# AlarmScrape.net
KiCad netlist of a schematic drawn in EAGLE
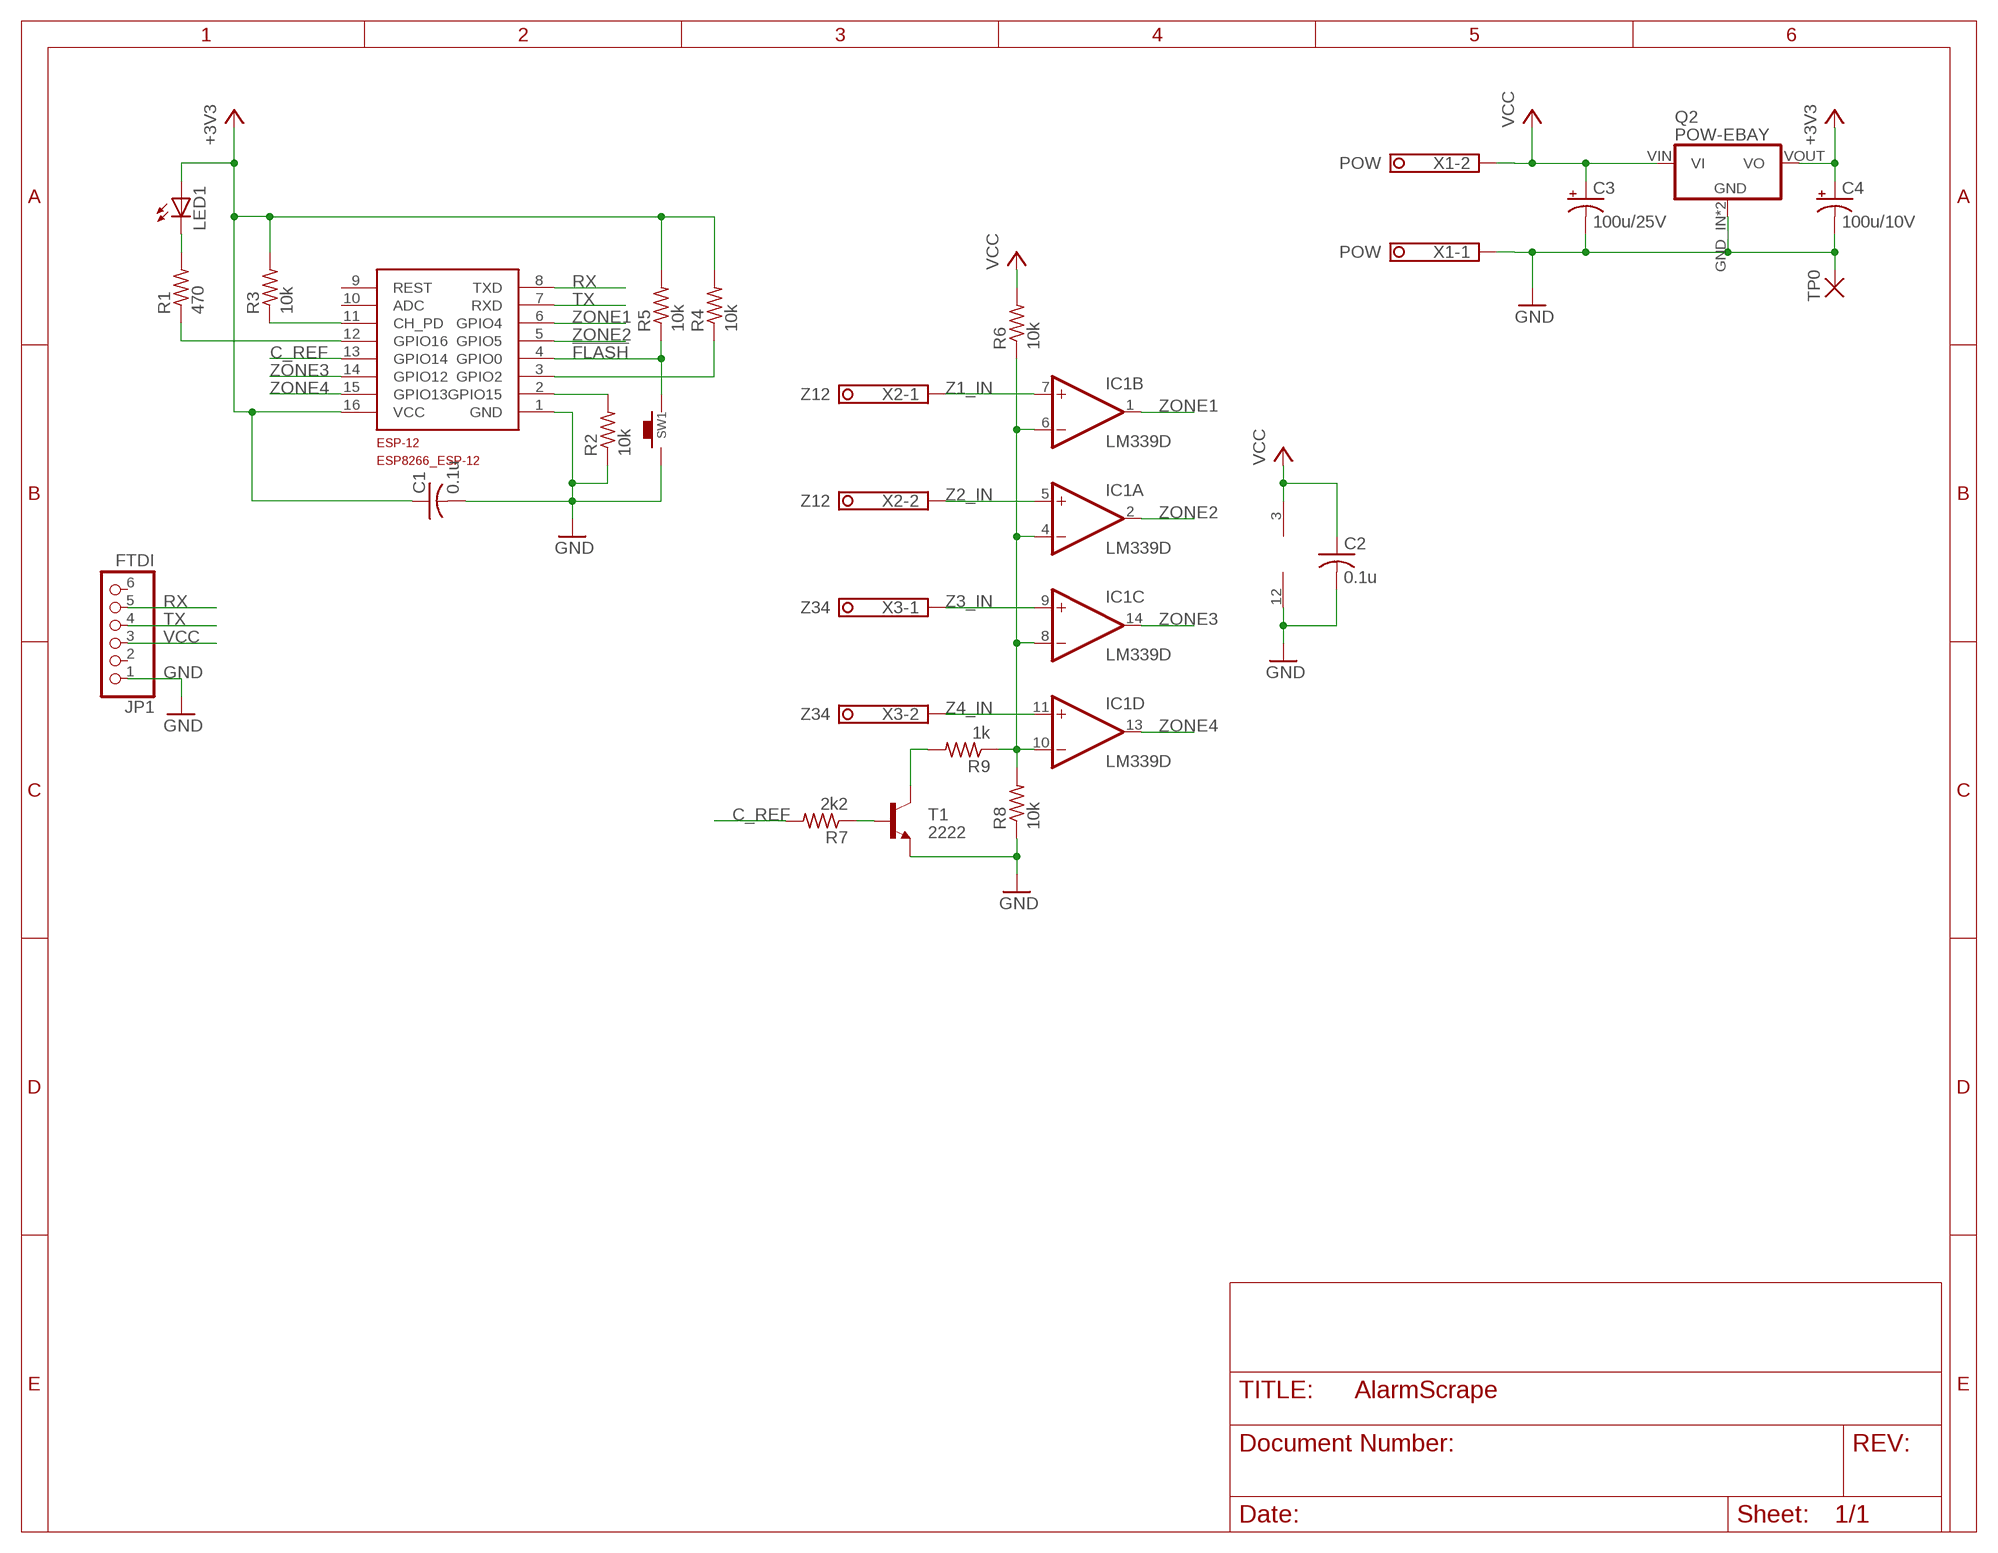
[diagram p0: schematic, sheet 1]

(export (version "E")
  (design (tool "Eeschema 10.0.6"))
  (components
    (comp (ref "C1")
      (value "0.1u")
      (footprint "eagle-import:C0805")
      (libsource (lib "eagle-import") (part "C-USC0805"))
    )
    (comp (ref "C2")
      (value "0.1u")
      (footprint "eagle-import:C0805")
      (libsource (lib "eagle-import") (part "C-USC0805"))
    )
    (comp (ref "C3")
      (value "100u/25V")
      (footprint "eagle-import:E2,5-6")
      (libsource (lib "eagle-import") (part "CPOL-USE2.5-6"))
    )
    (comp (ref "C4")
      (value "100u/10V")
      (footprint "eagle-import:E2,5-6")
      (libsource (lib "eagle-import") (part "CPOL-USE2.5-6"))
    )
    (comp (ref "ESP-12")
      (value "ESP8266_ESP-12")
      (footprint "eagle-import:ESP8266-ESP12")
      (libsource (lib "eagle-import") (part "ESP8266_ESP-12"))
    )
    (comp (ref "IC1")
      (value "LM339D")
      (footprint "eagle-import:SO14")
      (libsource (lib "eagle-import") (part "LM339D"))
    )
    (comp (ref "JP1")
      (value "FTDI")
      (footprint "eagle-import:1X06")
      (libsource (lib "eagle-import") (part "PINHD-1X6"))
    )
    (comp (ref "LED1")
      (value "LEDCHIPLED_0805")
      (footprint "eagle-import:CHIPLED_0805")
      (libsource (lib "eagle-import") (part "LEDCHIPLED_0805"))
    )
    (comp (ref "Q2")
      (value "POW-EBAY")
      (footprint "eagle-import:POW-BUCK-EBAY")
      (libsource (lib "eagle-import") (part "POW-EBAY"))
    )
    (comp (ref "R1")
      (value "470")
      (footprint "eagle-import:R0805")
      (libsource (lib "eagle-import") (part "R-US_R0805"))
    )
    (comp (ref "R2")
      (value "10k")
      (footprint "eagle-import:R0805")
      (libsource (lib "eagle-import") (part "R-US_R0805"))
    )
    (comp (ref "R3")
      (value "10k")
      (footprint "eagle-import:R0805")
      (libsource (lib "eagle-import") (part "R-US_R0805"))
    )
    (comp (ref "R4")
      (value "10k")
      (footprint "eagle-import:R0805")
      (libsource (lib "eagle-import") (part "R-US_R0805"))
    )
    (comp (ref "R5")
      (value "10k")
      (footprint "eagle-import:R0805")
      (libsource (lib "eagle-import") (part "R-US_R0805"))
    )
    (comp (ref "R6")
      (value "10k")
      (footprint "eagle-import:R0805")
      (libsource (lib "eagle-import") (part "R-US_R0805"))
    )
    (comp (ref "R7")
      (value "2k2")
      (footprint "eagle-import:R0805")
      (libsource (lib "eagle-import") (part "R-US_R0805"))
    )
    (comp (ref "R8")
      (value "10k")
      (footprint "eagle-import:R0805")
      (libsource (lib "eagle-import") (part "R-US_R0805"))
    )
    (comp (ref "R9")
      (value "1k")
      (footprint "eagle-import:R0805")
      (libsource (lib "eagle-import") (part "R-US_R0805"))
    )
    (comp (ref "SW1")
      (value "FLASH")
      (footprint "eagle-import:TACT-4X3")
      (libsource (lib "eagle-import") (part "TACTILE-2"))
    )
    (comp (ref "T1")
      (value "2222")
      (footprint "eagle-import:SOT23-3")
      (libsource (lib "eagle-import") (part "TRANSISTOR_NPNSOT23-3"))
    )
    (comp (ref "TP0")
      (value "THROUGH-HOLE")
      (footprint "eagle-import:PAD-032")
      (libsource (lib "eagle-import") (part "THROUGH-HOLE"))
    )
    (comp (ref "X1")
      (value "POW")
      (footprint "eagle-import:1751248")
      (libsource (lib "eagle-import") (part "1751248"))
    )
    (comp (ref "X2")
      (value "Z12")
      (footprint "eagle-import:1751248")
      (libsource (lib "eagle-import") (part "1751248"))
    )
    (comp (ref "X3")
      (value "Z34")
      (footprint "eagle-import:1751248")
      (libsource (lib "eagle-import") (part "1751248"))
    )
  )
  (nets
    (net (code "1") (name "+3V3") (class "Default")
      (node (ref "C1") (pin "1") (pinfunction "1_1") (pintype "passive"))
      (node (ref "C4") (pin "+") (pinfunction "+_+") (pintype "passive"))
      (node (ref "ESP-12") (pin "16") (pinfunction "VCC_16") (pintype "bidirectional"))
      (node (ref "LED1") (pin "A") (pinfunction "A_A") (pintype "passive"))
      (node (ref "Q2") (pin "VOUT") (pinfunction "VO_VOUT") (pintype "passive"))
      (node (ref "R3") (pin "2") (pinfunction "2_2") (pintype "passive"))
      (node (ref "R4") (pin "2") (pinfunction "2_2") (pintype "passive"))
      (node (ref "R5") (pin "2") (pinfunction "2_2") (pintype "passive"))
    )
    (net (code "2") (name "/C_REF") (class "Default")
      (node (ref "ESP-12") (pin "13") (pinfunction "GPIO14_13") (pintype "bidirectional"))
      (node (ref "R7") (pin "2") (pinfunction "2_2") (pintype "passive"))
    )
    (net (code "3") (name "/RX") (class "Default")
      (node (ref "ESP-12") (pin "8") (pinfunction "TXD_8") (pintype "bidirectional"))
      (node (ref "JP1") (pin "5") (pinfunction "5_5") (pintype "passive"))
    )
    (net (code "4") (name "/TX") (class "Default")
      (node (ref "ESP-12") (pin "7") (pinfunction "RXD_7") (pintype "bidirectional"))
      (node (ref "JP1") (pin "4") (pinfunction "4_4") (pintype "passive"))
    )
    (net (code "5") (name "/Z1_IN") (class "Default")
      (node (ref "IC1") (pin "7") (pinfunction "+IN_7") (pintype "input"))
      (node (ref "X2") (pin "1") (pinfunction "K_1") (pintype "passive"))
    )
    (net (code "6") (name "/Z2_IN") (class "Default")
      (node (ref "IC1") (pin "5") (pinfunction "+IN_5") (pintype "input"))
      (node (ref "X2") (pin "2") (pinfunction "K_2") (pintype "passive"))
    )
    (net (code "7") (name "/Z3_IN") (class "Default")
      (node (ref "IC1") (pin "9") (pinfunction "+IN_9") (pintype "input"))
      (node (ref "X3") (pin "1") (pinfunction "K_1") (pintype "passive"))
    )
    (net (code "8") (name "/Z4_IN") (class "Default")
      (node (ref "IC1") (pin "11") (pinfunction "+IN_11") (pintype "input"))
      (node (ref "X3") (pin "2") (pinfunction "K_2") (pintype "passive"))
    )
    (net (code "9") (name "/ZONE1") (class "Default")
      (node (ref "ESP-12") (pin "6") (pinfunction "GPIO4_6") (pintype "bidirectional"))
      (node (ref "IC1") (pin "1") (pinfunction "OUT_1") (pintype "open_collector"))
    )
    (net (code "10") (name "/ZONE2") (class "Default")
      (node (ref "ESP-12") (pin "5") (pinfunction "GPIO5_5") (pintype "bidirectional"))
      (node (ref "IC1") (pin "2") (pinfunction "OUT_2") (pintype "open_collector"))
    )
    (net (code "11") (name "/ZONE3") (class "Default")
      (node (ref "ESP-12") (pin "14") (pinfunction "GPIO12_14") (pintype "bidirectional"))
      (node (ref "IC1") (pin "14") (pinfunction "OUT_14") (pintype "open_collector"))
    )
    (net (code "12") (name "/ZONE4") (class "Default")
      (node (ref "ESP-12") (pin "15") (pinfunction "GPIO13_15") (pintype "bidirectional"))
      (node (ref "IC1") (pin "13") (pinfunction "OUT_13") (pintype "open_collector"))
    )
    (net (code "13") (name "/~{FLASH}") (class "Default")
      (node (ref "ESP-12") (pin "4") (pinfunction "GPIO0_4") (pintype "bidirectional"))
      (node (ref "R5") (pin "1") (pinfunction "1_1") (pintype "passive"))
      (node (ref "SW1") (pin "P1") (pinfunction "P1_P1") (pintype "bidirectional"))
    )
    (net (code "14") (name "GND") (class "Default")
      (node (ref "C1") (pin "2") (pinfunction "2_2") (pintype "passive"))
      (node (ref "C2") (pin "2") (pinfunction "2_2") (pintype "passive"))
      (node (ref "C3") (pin "-") (pinfunction "-_-") (pintype "passive"))
      (node (ref "C4") (pin "-") (pinfunction "-_-") (pintype "passive"))
      (node (ref "ESP-12") (pin "1") (pinfunction "GND_1") (pintype "bidirectional"))
      (node (ref "IC1") (pin "12") (pinfunction "GND_12") (pintype "power_in"))
      (node (ref "JP1") (pin "1") (pinfunction "1_1") (pintype "passive"))
      (node (ref "Q2") (pin "GND_IN") (pinfunction "GND_GND_IN") (pintype "passive"))
      (node (ref "Q2") (pin "GND_OUT") (pinfunction "GND_GND_OUT") (pintype "passive"))
      (node (ref "R2") (pin "1") (pinfunction "1_1") (pintype "passive"))
      (node (ref "R8") (pin "1") (pinfunction "1_1") (pintype "passive"))
      (node (ref "SW1") (pin "P0") (pinfunction "P0_P0") (pintype "bidirectional"))
      (node (ref "T1") (pin "2") (pinfunction "E_2") (pintype "passive"))
      (node (ref "TP0") (pin "P") (pinfunction "P_P") (pintype "output"))
      (node (ref "X1") (pin "1") (pinfunction "K_1") (pintype "passive"))
    )
    (net (code "15") (name "Net-(ESP-12-CH_PD)") (class "Default")
      (node (ref "ESP-12") (pin "11") (pinfunction "CH_PD_11") (pintype "bidirectional"))
      (node (ref "R3") (pin "1") (pinfunction "1_1") (pintype "passive"))
    )
    (net (code "16") (name "Net-(ESP-12-GPIO2)") (class "Default")
      (node (ref "ESP-12") (pin "3") (pinfunction "GPIO2_3") (pintype "bidirectional"))
      (node (ref "R4") (pin "1") (pinfunction "1_1") (pintype "passive"))
    )
    (net (code "17") (name "Net-(ESP-12-GPIO15)") (class "Default")
      (node (ref "ESP-12") (pin "2") (pinfunction "GPIO15_2") (pintype "bidirectional"))
      (node (ref "R2") (pin "2") (pinfunction "2_2") (pintype "passive"))
    )
    (net (code "18") (name "Net-(ESP-12-GPIO16)") (class "Default")
      (node (ref "ESP-12") (pin "12") (pinfunction "GPIO16_12") (pintype "bidirectional"))
      (node (ref "R1") (pin "1") (pinfunction "1_1") (pintype "passive"))
    )
    (net (code "19") (name "Net-(IC1A--IN)") (class "Default")
      (node (ref "IC1") (pin "10") (pinfunction "-IN_10") (pintype "input"))
      (node (ref "IC1") (pin "4") (pinfunction "-IN_4") (pintype "input"))
      (node (ref "IC1") (pin "6") (pinfunction "-IN_6") (pintype "input"))
      (node (ref "IC1") (pin "8") (pinfunction "-IN_8") (pintype "input"))
      (node (ref "R6") (pin "1") (pinfunction "1_1") (pintype "passive"))
      (node (ref "R8") (pin "2") (pinfunction "2_2") (pintype "passive"))
      (node (ref "R9") (pin "1") (pinfunction "1_1") (pintype "passive"))
    )
    (net (code "20") (name "Net-(LED1-PadC)") (class "Default")
      (node (ref "LED1") (pin "C") (pinfunction "C_C") (pintype "passive"))
      (node (ref "R1") (pin "2") (pinfunction "2_2") (pintype "passive"))
    )
    (net (code "21") (name "Net-(T1-B)") (class "Default")
      (node (ref "R7") (pin "1") (pinfunction "1_1") (pintype "passive"))
      (node (ref "T1") (pin "1") (pinfunction "B_1") (pintype "passive"))
    )
    (net (code "22") (name "Net-(T1-C)") (class "Default")
      (node (ref "R9") (pin "2") (pinfunction "2_2") (pintype "passive"))
      (node (ref "T1") (pin "3") (pinfunction "C_3") (pintype "passive"))
    )
    (net (code "23") (name "VCC") (class "Default")
      (node (ref "C2") (pin "1") (pinfunction "1_1") (pintype "passive"))
      (node (ref "C3") (pin "+") (pinfunction "+_+") (pintype "passive"))
      (node (ref "IC1") (pin "3") (pinfunction "V+_3") (pintype "power_in"))
      (node (ref "JP1") (pin "3") (pinfunction "3_3") (pintype "passive"))
      (node (ref "Q2") (pin "VIN") (pinfunction "VI_VIN") (pintype "input"))
      (node (ref "R6") (pin "2") (pinfunction "2_2") (pintype "passive"))
      (node (ref "X1") (pin "2") (pinfunction "K_2") (pintype "passive"))
    )
    (net (code "24") (name "unconnected-(ESP-12-ADC-Pad10)") (class "Default")
      (node (ref "ESP-12") (pin "10") (pinfunction "ADC_10") (pintype "bidirectional"))
    )
    (net (code "25") (name "unconnected-(ESP-12-REST-Pad9)") (class "Default")
      (node (ref "ESP-12") (pin "9") (pinfunction "REST_9") (pintype "bidirectional"))
    )
    (net (code "26") (name "unconnected-(JP1-Pad2)") (class "Default")
      (node (ref "JP1") (pin "2") (pinfunction "2_2") (pintype "passive"))
    )
    (net (code "27") (name "unconnected-(JP1-Pad6)") (class "Default")
      (node (ref "JP1") (pin "6") (pinfunction "6_6") (pintype "passive"))
    )
  )
)
